# whammy-schematic.net
KiCad netlist of a schematic drawn in EAGLE
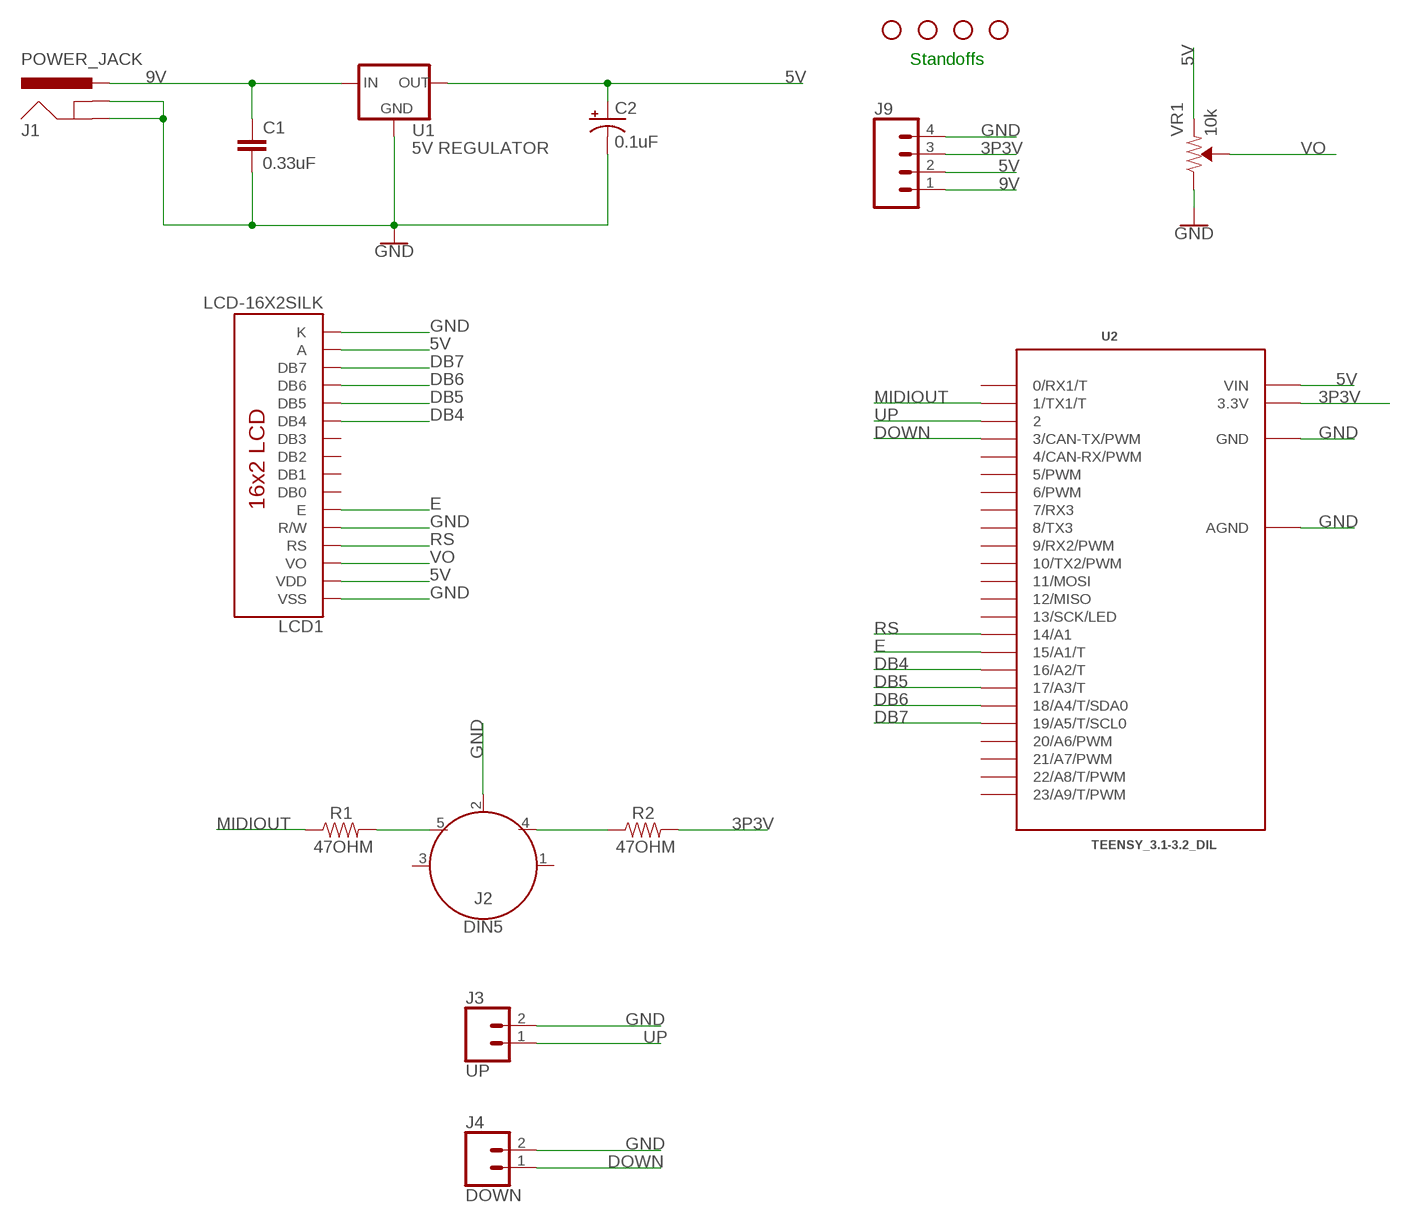
[diagram p0: schematic, sheet 1]

(export (version "E")
  (design (tool "Eeschema 10.0.6"))
  (components
    (comp (ref "C1")
      (value "0.33uF")
      (footprint "eagle-import:CAP-PTH-2.54")
      (libsource (lib "eagle-import") (part "22PF-PTH-2.54MM-200V-5%"))
    )
    (comp (ref "C2")
      (value "0.1uF")
      (footprint "eagle-import:CPOL-RADIAL-2.5MM-5MM")
      (libsource (lib "eagle-import") (part "10UF-POLAR-RADIAL-2.5MM-25V-20%"))
    )
    (comp (ref "H1")
      (value "STAND-OFF")
      (footprint "eagle-import:STAND-OFF")
      (libsource (lib "eagle-import") (part "STAND-OFF"))
    )
    (comp (ref "H2")
      (value "STAND-OFF")
      (footprint "eagle-import:STAND-OFF")
      (libsource (lib "eagle-import") (part "STAND-OFF"))
    )
    (comp (ref "H3")
      (value "STAND-OFF")
      (footprint "eagle-import:STAND-OFF")
      (libsource (lib "eagle-import") (part "STAND-OFF"))
    )
    (comp (ref "H4")
      (value "STAND-OFF")
      (footprint "eagle-import:STAND-OFF")
      (libsource (lib "eagle-import") (part "STAND-OFF"))
    )
    (comp (ref "J1")
      (value "POWER_JACK")
      (footprint "eagle-import:POWER_JACK_PTH")
      (libsource (lib "eagle-import") (part "POWER_JACK"))
    )
    (comp (ref "J2")
      (value "DIN5")
      (footprint "eagle-import:DIN5-RA-PTH")
      (libsource (lib "eagle-import") (part "DIN5"))
    )
    (comp (ref "J3")
      (value "UP")
      (footprint "eagle-import:1X02")
      (libsource (lib "eagle-import") (part "CONN_02"))
    )
    (comp (ref "J4")
      (value "DOWN")
      (footprint "eagle-import:1X02")
      (libsource (lib "eagle-import") (part "CONN_02"))
    )
    (comp (ref "J9")
      (value "CONN_04")
      (footprint "eagle-import:1X04")
      (libsource (lib "eagle-import") (part "CONN_04"))
    )
    (comp (ref "LCD1")
      (value "LCD-16X2SILK")
      (footprint "eagle-import:LCD-16X2")
      (libsource (lib "eagle-import") (part "LCD-16X2SILK"))
    )
    (comp (ref "R1")
      (value "47OHM")
      (footprint "eagle-import:AXIAL-0.3-KIT")
      (libsource (lib "eagle-import") (part "RESISTORAXIAL-0.3-KIT"))
    )
    (comp (ref "R2")
      (value "47OHM")
      (footprint "eagle-import:AXIAL-0.3-KIT")
      (libsource (lib "eagle-import") (part "RESISTORAXIAL-0.3-KIT"))
    )
    (comp (ref "U1")
      (value "5V REGULATOR")
      (footprint "eagle-import:TO-220-ALT")
      (libsource (lib "eagle-import") (part "V_REG_78XX-TO-220"))
    )
    (comp (ref "U2")
      (value "TEENSY_3.1-3.2_DIL")
      (footprint "eagle-import:TEENSY_3.0-3.2&LC_DIL")
      (libsource (lib "eagle-import") (part "TEENSY_3.1-3.2_DIL"))
    )
    (comp (ref "VR1")
      (value "10k")
      (footprint "eagle-import:TRIMPOT-PTH-3386U")
      (libsource (lib "eagle-import") (part "TRIMPOT-PTH-10MM-KNOB-1/2W-10%"))
    )
  )
  (nets
    (net (code "1") (name "/3P3V") (class "Default")
      (node (ref "J9") (pin "3") (pinfunction "3_3") (pintype "passive"))
      (node (ref "R2") (pin "P$2") (pinfunction "2_P$2") (pintype "passive"))
      (node (ref "U2") (pin "3.3V") (pinfunction "3.3V_3.3V") (pintype "power_in"))
    )
    (net (code "2") (name "/5V") (class "Default")
      (node (ref "C2") (pin "1") (pinfunction "+_1") (pintype "passive"))
      (node (ref "J9") (pin "2") (pinfunction "2_2") (pintype "passive"))
      (node (ref "LCD1") (pin "15") (pinfunction "A_15") (pintype "power_in"))
      (node (ref "LCD1") (pin "2") (pinfunction "VDD_2") (pintype "power_in"))
      (node (ref "U1") (pin "OUT") (pinfunction "OUT_OUT") (pintype "passive"))
      (node (ref "U2") (pin "VIN") (pinfunction "VIN_VIN") (pintype "power_in"))
      (node (ref "VR1") (pin "1") (pinfunction "CCW_1") (pintype "passive"))
    )
    (net (code "3") (name "/9V") (class "Default")
      (node (ref "C1") (pin "1") (pinfunction "1_1") (pintype "passive"))
      (node (ref "J1") (pin "PWR") (pinfunction "PWR_PWR") (pintype "bidirectional"))
      (node (ref "J9") (pin "1") (pinfunction "1_1") (pintype "passive"))
      (node (ref "U1") (pin "IN") (pinfunction "IN_IN") (pintype "input"))
    )
    (net (code "4") (name "/DB4") (class "Default")
      (node (ref "LCD1") (pin "11") (pinfunction "DB4_11") (pintype "bidirectional"))
      (node (ref "U2") (pin "16/A2") (pinfunction "16/A2/T_16/A2") (pintype "bidirectional"))
    )
    (net (code "5") (name "/DB5") (class "Default")
      (node (ref "LCD1") (pin "12") (pinfunction "DB5_12") (pintype "bidirectional"))
      (node (ref "U2") (pin "17/A3") (pinfunction "17/A3/T_17/A3") (pintype "bidirectional"))
    )
    (net (code "6") (name "/DB6") (class "Default")
      (node (ref "LCD1") (pin "13") (pinfunction "DB6_13") (pintype "bidirectional"))
      (node (ref "U2") (pin "18/A4") (pinfunction "18/A4/T/SDA0_18/A4") (pintype "bidirectional"))
    )
    (net (code "7") (name "/DB7") (class "Default")
      (node (ref "LCD1") (pin "14") (pinfunction "DB7_14") (pintype "bidirectional"))
      (node (ref "U2") (pin "19/A5") (pinfunction "19/A5/T/SCL0_19/A5") (pintype "bidirectional"))
    )
    (net (code "8") (name "/DOWN") (class "Default")
      (node (ref "J4") (pin "1") (pinfunction "1_1") (pintype "passive"))
      (node (ref "U2") (pin "3") (pinfunction "3/CAN-TX/PWM_3") (pintype "bidirectional"))
    )
    (net (code "9") (name "/E") (class "Default")
      (node (ref "LCD1") (pin "6") (pinfunction "E_6") (pintype "input"))
      (node (ref "U2") (pin "15/A1") (pinfunction "15/A1/T_15/A1") (pintype "bidirectional"))
    )
    (net (code "10") (name "/MIDIOUT") (class "Default")
      (node (ref "R1") (pin "P$1") (pinfunction "1_P$1") (pintype "passive"))
      (node (ref "U2") (pin "1") (pinfunction "1/TX1/T_1") (pintype "bidirectional"))
    )
    (net (code "11") (name "/RS") (class "Default")
      (node (ref "LCD1") (pin "4") (pinfunction "RS_4") (pintype "input"))
      (node (ref "U2") (pin "14/A0") (pinfunction "14/A1_14/A0") (pintype "bidirectional"))
    )
    (net (code "12") (name "/UP") (class "Default")
      (node (ref "J3") (pin "1") (pinfunction "1_1") (pintype "passive"))
      (node (ref "U2") (pin "2") (pinfunction "2_2") (pintype "bidirectional"))
    )
    (net (code "13") (name "/VO") (class "Default")
      (node (ref "LCD1") (pin "3") (pinfunction "VO_3") (pintype "bidirectional"))
      (node (ref "VR1") (pin "2") (pinfunction "WIPER_2") (pintype "passive"))
    )
    (net (code "14") (name "GND") (class "Default")
      (node (ref "C1") (pin "2") (pinfunction "2_2") (pintype "passive"))
      (node (ref "C2") (pin "2") (pinfunction "-_2") (pintype "passive"))
      (node (ref "J1") (pin "GND") (pinfunction "GND_GND") (pintype "bidirectional"))
      (node (ref "J1") (pin "GNDBREAK") (pinfunction "GNDBREAK_GNDBREAK") (pintype "bidirectional"))
      (node (ref "J2") (pin "2") (pinfunction "2_2") (pintype "bidirectional"))
      (node (ref "J3") (pin "2") (pinfunction "2_2") (pintype "passive"))
      (node (ref "J4") (pin "2") (pinfunction "2_2") (pintype "passive"))
      (node (ref "J9") (pin "4") (pinfunction "4_4") (pintype "passive"))
      (node (ref "LCD1") (pin "1") (pinfunction "VSS_1") (pintype "power_in"))
      (node (ref "LCD1") (pin "16") (pinfunction "K_16") (pintype "power_in"))
      (node (ref "LCD1") (pin "5") (pinfunction "R/W_5") (pintype "input"))
      (node (ref "U1") (pin "GND") (pinfunction "GND_GND") (pintype "input"))
      (node (ref "U2") (pin "AGND") (pinfunction "AGND_AGND") (pintype "power_in"))
      (node (ref "U2") (pin "GND") (pinfunction "GND_GND") (pintype "power_in"))
      (node (ref "VR1") (pin "3") (pinfunction "CW_3") (pintype "passive"))
    )
    (net (code "15") (name "Net-(R1-2)") (class "Default")
      (node (ref "J2") (pin "5") (pinfunction "5_5") (pintype "bidirectional"))
      (node (ref "R1") (pin "P$2") (pinfunction "2_P$2") (pintype "passive"))
    )
    (net (code "16") (name "Net-(R2-1)") (class "Default")
      (node (ref "J2") (pin "4") (pinfunction "4_4") (pintype "bidirectional"))
      (node (ref "R2") (pin "P$1") (pinfunction "1_P$1") (pintype "passive"))
    )
    (net (code "17") (name "unconnected-(J2-Pad1)") (class "Default")
      (node (ref "J2") (pin "1") (pinfunction "1_1") (pintype "bidirectional"))
    )
    (net (code "18") (name "unconnected-(J2-Pad3)") (class "Default")
      (node (ref "J2") (pin "3") (pinfunction "3_3") (pintype "bidirectional"))
    )
    (net (code "19") (name "unconnected-(LCD1-DB0-Pad7)") (class "Default")
      (node (ref "LCD1") (pin "7") (pinfunction "DB0_7") (pintype "bidirectional"))
    )
    (net (code "20") (name "unconnected-(LCD1-DB1-Pad8)") (class "Default")
      (node (ref "LCD1") (pin "8") (pinfunction "DB1_8") (pintype "bidirectional"))
    )
    (net (code "21") (name "unconnected-(LCD1-DB2-Pad9)") (class "Default")
      (node (ref "LCD1") (pin "9") (pinfunction "DB2_9") (pintype "bidirectional"))
    )
    (net (code "22") (name "unconnected-(LCD1-DB3-Pad10)") (class "Default")
      (node (ref "LCD1") (pin "10") (pinfunction "DB3_10") (pintype "bidirectional"))
    )
    (net (code "23") (name "unconnected-(U2-0{slash}RX1{slash}T-Pad0)") (class "Default")
      (node (ref "U2") (pin "0") (pinfunction "0/RX1/T_0") (pintype "bidirectional"))
    )
    (net (code "24") (name "unconnected-(U2-4{slash}CAN-RX{slash}PWM-Pad4)") (class "Default")
      (node (ref "U2") (pin "4") (pinfunction "4/CAN-RX/PWM_4") (pintype "bidirectional"))
    )
    (net (code "25") (name "unconnected-(U2-5{slash}PWM-Pad5)") (class "Default")
      (node (ref "U2") (pin "5") (pinfunction "5/PWM_5") (pintype "bidirectional"))
    )
    (net (code "26") (name "unconnected-(U2-6{slash}PWM-Pad6)") (class "Default")
      (node (ref "U2") (pin "6") (pinfunction "6/PWM_6") (pintype "bidirectional"))
    )
    (net (code "27") (name "unconnected-(U2-7{slash}RX3-Pad7)") (class "Default")
      (node (ref "U2") (pin "7") (pinfunction "7/RX3_7") (pintype "bidirectional"))
    )
    (net (code "28") (name "unconnected-(U2-8{slash}TX3-Pad8)") (class "Default")
      (node (ref "U2") (pin "8") (pinfunction "8/TX3_8") (pintype "bidirectional"))
    )
    (net (code "29") (name "unconnected-(U2-9{slash}RX2{slash}PWM-Pad9)") (class "Default")
      (node (ref "U2") (pin "9") (pinfunction "9/RX2/PWM_9") (pintype "bidirectional"))
    )
    (net (code "30") (name "unconnected-(U2-10{slash}TX2{slash}PWM-Pad10)") (class "Default")
      (node (ref "U2") (pin "10") (pinfunction "10/TX2/PWM_10") (pintype "bidirectional"))
    )
    (net (code "31") (name "unconnected-(U2-11{slash}MOSI-Pad11)") (class "Default")
      (node (ref "U2") (pin "11") (pinfunction "11/MOSI_11") (pintype "bidirectional"))
    )
    (net (code "32") (name "unconnected-(U2-12{slash}MISO-Pad12)") (class "Default")
      (node (ref "U2") (pin "12") (pinfunction "12/MISO_12") (pintype "bidirectional"))
    )
    (net (code "33") (name "unconnected-(U2-13{slash}SCK{slash}LED-Pad13)") (class "Default")
      (node (ref "U2") (pin "13") (pinfunction "13/SCK/LED_13") (pintype "bidirectional"))
    )
    (net (code "34") (name "unconnected-(U2-20{slash}A6{slash}PWM-Pad20{slash}A6)") (class "Default")
      (node (ref "U2") (pin "20/A6") (pinfunction "20/A6/PWM_20/A6") (pintype "bidirectional"))
    )
    (net (code "35") (name "unconnected-(U2-21{slash}A7{slash}PWM-Pad21{slash}A7)") (class "Default")
      (node (ref "U2") (pin "21/A7") (pinfunction "21/A7/PWM_21/A7") (pintype "bidirectional"))
    )
    (net (code "36") (name "unconnected-(U2-22{slash}A8{slash}T{slash}PWM-Pad22{slash}A8)") (class "Default")
      (node (ref "U2") (pin "22/A8") (pinfunction "22/A8/T/PWM_22/A8") (pintype "bidirectional"))
    )
    (net (code "37") (name "unconnected-(U2-23{slash}A9{slash}T{slash}PWM-Pad23{slash}A9)") (class "Default")
      (node (ref "U2") (pin "23/A9") (pinfunction "23/A9/T/PWM_23/A9") (pintype "bidirectional"))
    )
  )
)
